# Power.net
KiCad netlist of a schematic drawn in Altium Designer
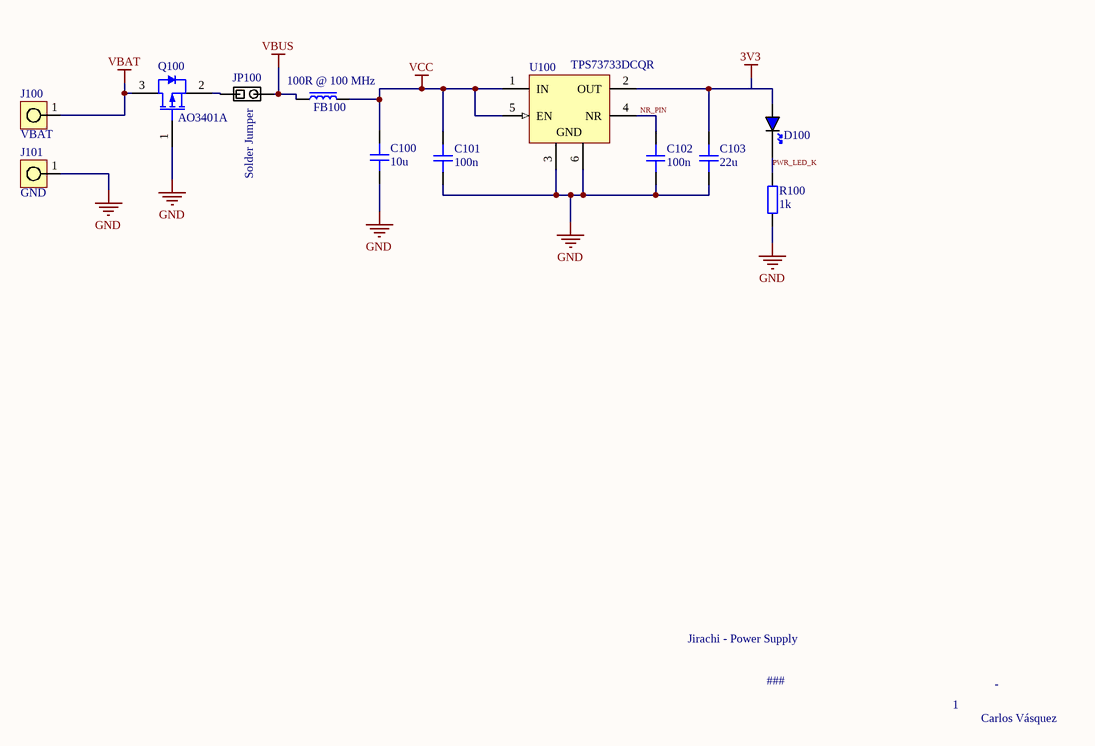
[diagram p0: Power.SchDoc]

(export (version "E")
  (design (tool "Eeschema 10.0.6"))
  (components
    (comp (ref "C100")
      (value "10u")
      (footprint "CAP_0805")
      (description "Capacitor SMD 0805")
      (libsource (lib "Schematic-Lib-PhilsLab") (part "CAP_0805"))
    )
    (comp (ref "C101")
      (value "100n")
      (footprint "CAP_0603")
      (description "Capacitor SMD 0603")
      (libsource (lib "Schematic-Lib-PhilsLab") (part "CAP_0603"))
    )
    (comp (ref "C102")
      (value "100n")
      (footprint "CAP_0603")
      (description "Capacitor SMD 0603")
      (libsource (lib "Schematic-Lib-PhilsLab") (part "CAP_0603"))
    )
    (comp (ref "C103")
      (value "22u")
      (footprint "CAP_0603")
      (description "Capacitor SMD 0603")
      (libsource (lib "Schematic-Lib-PhilsLab") (part "CAP_0603"))
    )
    (comp (ref "D100")
      (value "BLUE")
      (footprint "LED_0805_BLUE")
      (description "LED 0805 BLUE SMD")
      (libsource (lib "Schematic-Lib-PhilsLab") (part "LED_0805_BLUE"))
    )
    (comp (ref "FB100")
      (value "100R @ 100 MHz")
      (footprint "FB_0805")
      (description "Ferrite Bead SMD 0805")
      (libsource (lib "Schematic-Lib-PhilsLab") (part "FB_0805"))
    )
    (comp (ref "J100")
      (value "VBAT")
      (footprint "SOLDER_PIN_THT_1_5")
      (description "Solder Pin 1.5mm Through-Hole")
      (libsource (lib "Schematic-Lib-PhilsLab") (part "SOLDER_PIN_THT"))
    )
    (comp (ref "J101")
      (value "GND")
      (footprint "SOLDER_PIN_THT_1_5")
      (description "Solder Pin 1.5mm Through-Hole")
      (libsource (lib "Schematic-Lib-PhilsLab") (part "SOLDER_PIN_THT"))
    )
    (comp (ref "JP100")
      (value "Solder Jumper")
      (footprint "SolderJumper_Single")
      (description "Solder Jumper Single 0.5mm Pitch")
      (libsource (lib "Schematic-Lib-PhilsLab") (part "SolderJumper_Single"))
    )
    (comp (ref "Q100")
      (value "AO3401A")
      (footprint "AO-SOT-23-3L_V")
      (description "P-Channel MOSFET, 30 V, 4 A, -55 to 150 degC, 3-Pin SOT-23-3L, RoHS, Tape and Reel")
      (fields (field (name "MANUFACTURER") "Alpha and Omega"))
      (libsource (lib "Altium Content Vault") (part "PEMOS-GSD-3"))
    )
    (comp (ref "R100")
      (value "1k")
      (footprint "RES_0402")
      (description "Resistor SMD 0402")
      (libsource (lib "Schematic-Lib-PhilsLab") (part "RES_0402"))
    )
    (comp (ref "U100")
      (value "TPS73733DCQR")
      (footprint "DCQ0006A_N")
      (fields (field (name "MANUFACTURER") "Texas Instruments"))
      (libsource (lib "Altium Content Vault") (part "TI-TPS73XXXDCQ6"))
    )
  )
  (nets
    (net (code "1") (name "/NR_PIN") (class "Default")
      (node (ref "C102") (pin "2") (pinfunction "2_2") (pintype "passive"))
      (node (ref "U100") (pin "4") (pinfunction "NR_4") (pintype "passive"))
    )
    (net (code "2") (name "/PWR_LED_K") (class "Default")
      (node (ref "D100") (pin "K") (pinfunction "K_K") (pintype "passive"))
      (node (ref "R100") (pin "2") (pinfunction "2_2") (pintype "passive"))
    )
    (net (code "3") (name "3V3") (class "Default")
      (node (ref "C103") (pin "2") (pinfunction "2_2") (pintype "passive"))
      (node (ref "D100") (pin "A") (pinfunction "A_A") (pintype "passive"))
      (node (ref "U100") (pin "2") (pinfunction "OUT_2") (pintype "power_in"))
    )
    (net (code "4") (name "GND") (class "Default")
      (node (ref "C100") (pin "1") (pinfunction "1_1") (pintype "passive"))
      (node (ref "C101") (pin "1") (pinfunction "1_1") (pintype "passive"))
      (node (ref "C102") (pin "1") (pinfunction "1_1") (pintype "passive"))
      (node (ref "C103") (pin "1") (pinfunction "1_1") (pintype "passive"))
      (node (ref "J101") (pin "1") (pinfunction "1_1") (pintype "passive"))
      (node (ref "Q100") (pin "1") (pinfunction "GATE_1") (pintype "passive"))
      (node (ref "R100") (pin "1") (pinfunction "1_1") (pintype "passive"))
      (node (ref "U100") (pin "3") (pinfunction "GND_3") (pintype "power_in"))
      (node (ref "U100") (pin "6") (pinfunction "GND_6") (pintype "power_in"))
    )
    (net (code "5") (name "Net-(Q100-SOURCE)") (class "Default")
      (node (ref "JP100") (pin "1") (pinfunction "1_1") (pintype "passive"))
      (node (ref "Q100") (pin "2") (pinfunction "SOURCE_2") (pintype "passive"))
    )
    (net (code "6") (name "VBAT") (class "Default")
      (node (ref "J100") (pin "1") (pinfunction "1_1") (pintype "passive"))
      (node (ref "Q100") (pin "3") (pinfunction "DRAIN_3") (pintype "passive"))
    )
    (net (code "7") (name "VBUS") (class "Default")
      (node (ref "FB100") (pin "1") (pinfunction "1_1") (pintype "passive"))
      (node (ref "JP100") (pin "2") (pinfunction "2_2") (pintype "passive"))
    )
    (net (code "8") (name "VCC") (class "Default")
      (node (ref "C100") (pin "2") (pinfunction "2_2") (pintype "passive"))
      (node (ref "C101") (pin "2") (pinfunction "2_2") (pintype "passive"))
      (node (ref "FB100") (pin "2") (pinfunction "2_2") (pintype "passive"))
      (node (ref "U100") (pin "1") (pinfunction "IN_1") (pintype "power_in"))
      (node (ref "U100") (pin "5") (pinfunction "EN_5") (pintype "input"))
    )
  )
)
